# LDO.net
KiCad netlist of a schematic drawn in Altium Designer
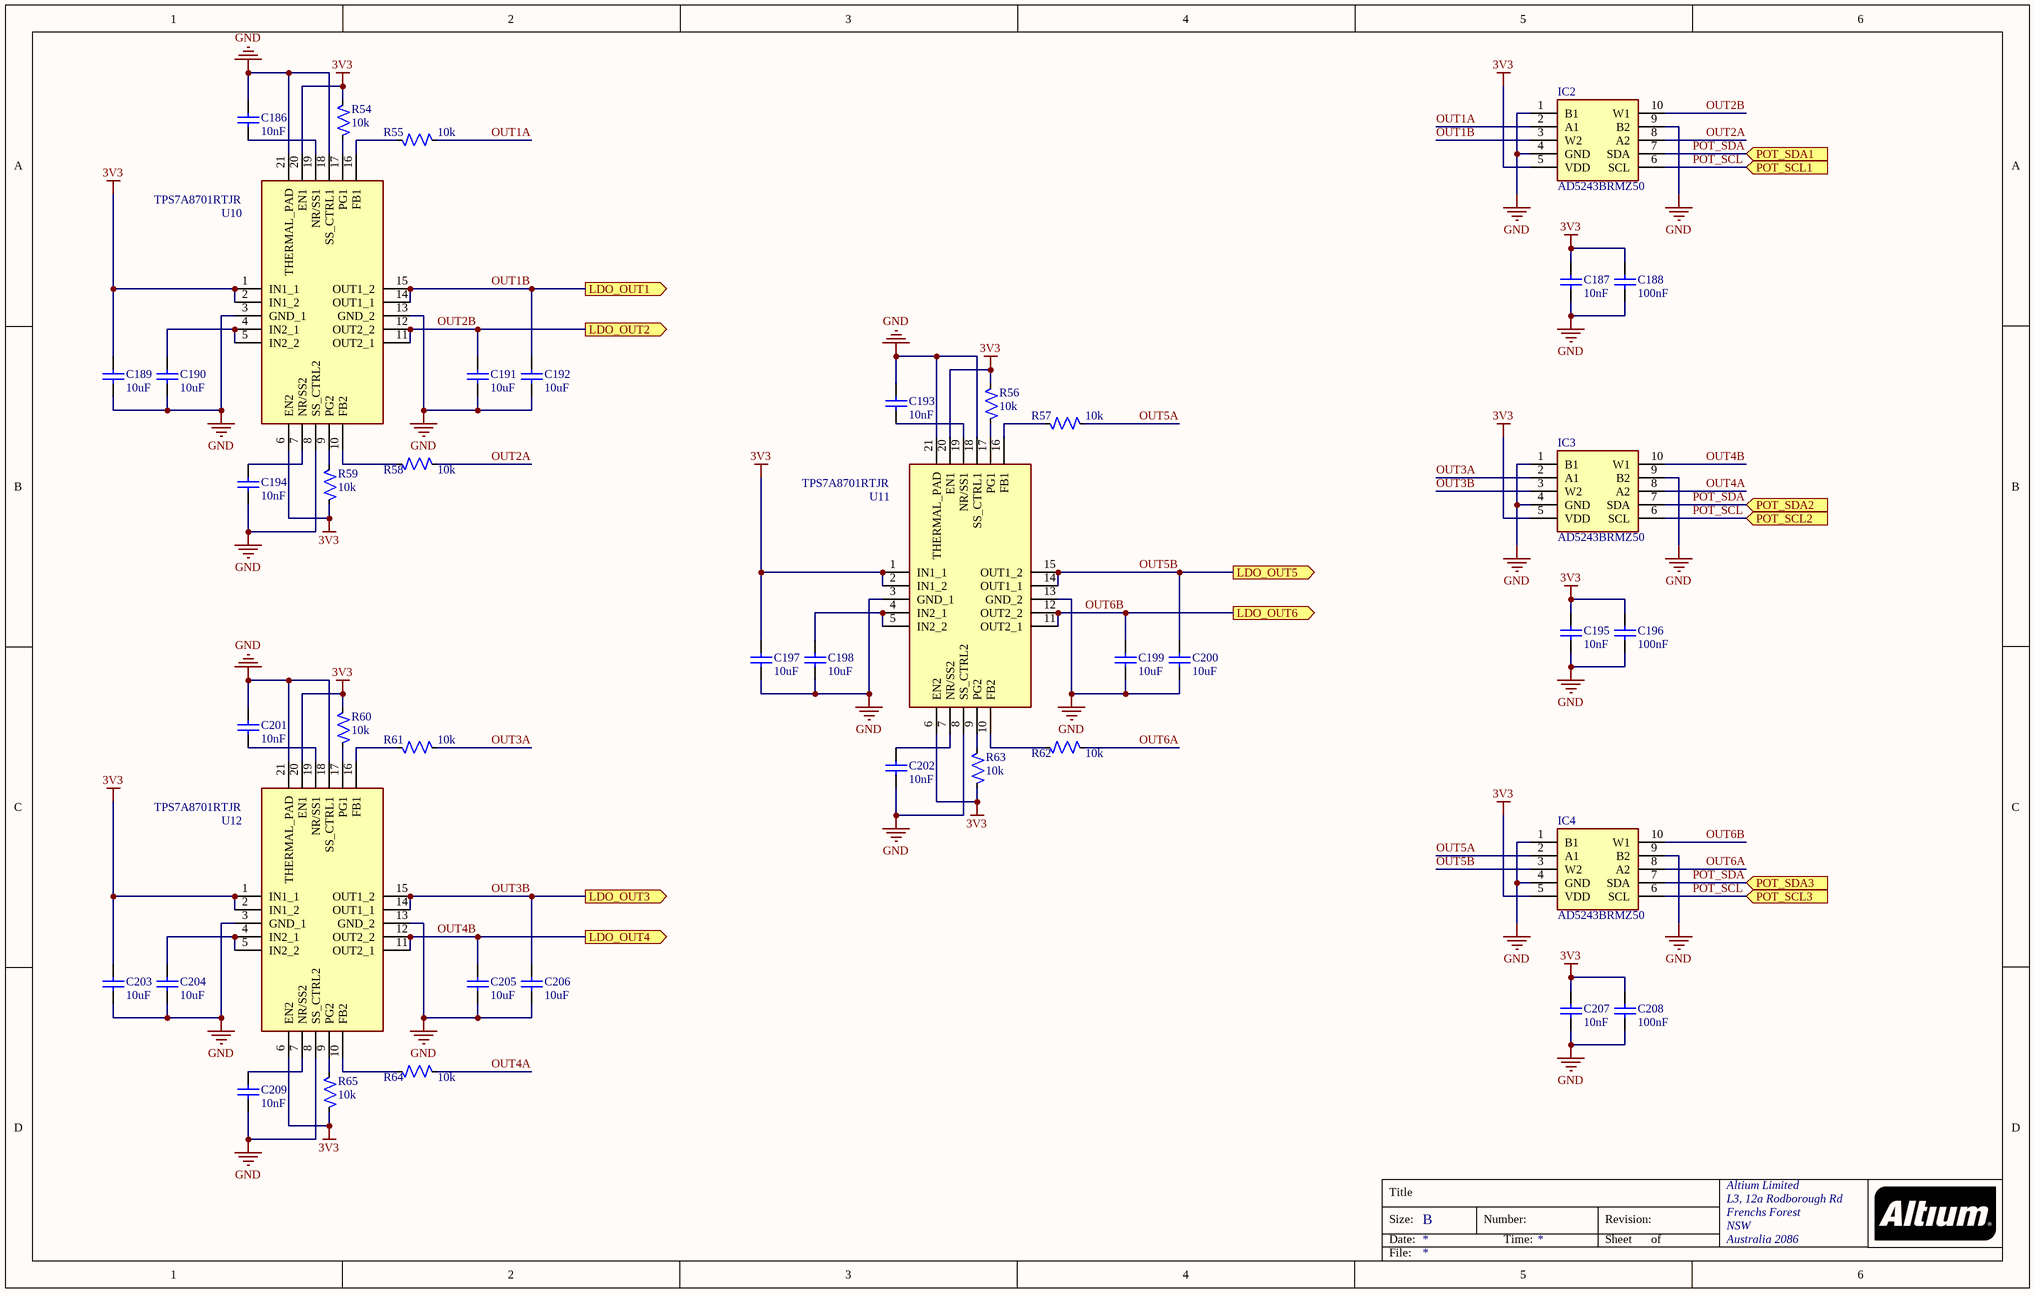
[diagram p0: LDO.SchDoc]

(export (version "E")
  (design (tool "Eeschema 10.0.6"))
  (components
    (comp (ref "C186")
      (value "10nF")
      (footprint "CAPC0402(1005)60_N")
      (libsource (lib "my_schsymbols") (part "CAP_0402"))
    )
    (comp (ref "C187")
      (value "10nF")
      (footprint "CAPC0402(1005)60_N")
      (libsource (lib "my_schsymbols") (part "CAP_0402"))
    )
    (comp (ref "C188")
      (value "100nF")
      (footprint "CAPC0402(1005)60_N")
      (libsource (lib "my_schsymbols") (part "CAP_0402"))
    )
    (comp (ref "C189")
      (value "10uF")
      (footprint "CAPC0805(2012)145_N")
      (libsource (lib "my_schsymbols") (part "CAP_0805"))
    )
    (comp (ref "C190")
      (value "10uF")
      (footprint "CAPC0805(2012)145_N")
      (libsource (lib "my_schsymbols") (part "CAP_0805"))
    )
    (comp (ref "C191")
      (value "10uF")
      (footprint "CAPC0805(2012)145_N")
      (libsource (lib "my_schsymbols") (part "CAP_0805"))
    )
    (comp (ref "C192")
      (value "10uF")
      (footprint "CAPC0805(2012)145_N")
      (libsource (lib "my_schsymbols") (part "CAP_0805"))
    )
    (comp (ref "C193")
      (value "10nF")
      (footprint "CAPC0402(1005)60_N")
      (libsource (lib "my_schsymbols") (part "CAP_0402"))
    )
    (comp (ref "C194")
      (value "10nF")
      (footprint "CAPC0402(1005)60_N")
      (libsource (lib "my_schsymbols") (part "CAP_0402"))
    )
    (comp (ref "C195")
      (value "10nF")
      (footprint "CAPC0402(1005)60_N")
      (libsource (lib "my_schsymbols") (part "CAP_0402"))
    )
    (comp (ref "C196")
      (value "100nF")
      (footprint "CAPC0402(1005)60_N")
      (libsource (lib "my_schsymbols") (part "CAP_0402"))
    )
    (comp (ref "C197")
      (value "10uF")
      (footprint "CAPC0805(2012)145_N")
      (libsource (lib "my_schsymbols") (part "CAP_0805"))
    )
    (comp (ref "C198")
      (value "10uF")
      (footprint "CAPC0805(2012)145_N")
      (libsource (lib "my_schsymbols") (part "CAP_0805"))
    )
    (comp (ref "C199")
      (value "10uF")
      (footprint "CAPC0805(2012)145_N")
      (libsource (lib "my_schsymbols") (part "CAP_0805"))
    )
    (comp (ref "C200")
      (value "10uF")
      (footprint "CAPC0805(2012)145_N")
      (libsource (lib "my_schsymbols") (part "CAP_0805"))
    )
    (comp (ref "C201")
      (value "10nF")
      (footprint "CAPC0402(1005)60_N")
      (libsource (lib "my_schsymbols") (part "CAP_0402"))
    )
    (comp (ref "C202")
      (value "10nF")
      (footprint "CAPC0402(1005)60_N")
      (libsource (lib "my_schsymbols") (part "CAP_0402"))
    )
    (comp (ref "C203")
      (value "10uF")
      (footprint "CAPC0805(2012)145_N")
      (libsource (lib "my_schsymbols") (part "CAP_0805"))
    )
    (comp (ref "C204")
      (value "10uF")
      (footprint "CAPC0805(2012)145_N")
      (libsource (lib "my_schsymbols") (part "CAP_0805"))
    )
    (comp (ref "C205")
      (value "10uF")
      (footprint "CAPC0805(2012)145_N")
      (libsource (lib "my_schsymbols") (part "CAP_0805"))
    )
    (comp (ref "C206")
      (value "10uF")
      (footprint "CAPC0805(2012)145_N")
      (libsource (lib "my_schsymbols") (part "CAP_0805"))
    )
    (comp (ref "C207")
      (value "10nF")
      (footprint "CAPC0402(1005)60_N")
      (libsource (lib "my_schsymbols") (part "CAP_0402"))
    )
    (comp (ref "C208")
      (value "100nF")
      (footprint "CAPC0402(1005)60_N")
      (libsource (lib "my_schsymbols") (part "CAP_0402"))
    )
    (comp (ref "C209")
      (value "10nF")
      (footprint "CAPC0402(1005)60_N")
      (libsource (lib "my_schsymbols") (part "CAP_0402"))
    )
    (comp (ref "IC2")
      (value "AD5243BRMZ50")
      (footprint "SamacSys:SOP50P490X110-10N")
      (description "Integrated Circuit")
      (fields
        (field (name "MOUSER PART NUMBER") "584-AD5243BRMZ50")
        (field (name "RS PART NUMBER") "9126564")
      )
      (libsource (lib "*") (part "AD5243BRMZ50"))
    )
    (comp (ref "IC3")
      (value "AD5243BRMZ50")
      (footprint "SamacSys:SOP50P490X110-10N")
      (description "Integrated Circuit")
      (fields
        (field (name "MOUSER PART NUMBER") "584-AD5243BRMZ50")
        (field (name "RS PART NUMBER") "9126564")
      )
      (libsource (lib "*") (part "AD5243BRMZ50"))
    )
    (comp (ref "IC4")
      (value "AD5243BRMZ50")
      (footprint "SamacSys:SOP50P490X110-10N")
      (description "Integrated Circuit")
      (fields
        (field (name "MOUSER PART NUMBER") "584-AD5243BRMZ50")
        (field (name "RS PART NUMBER") "9126564")
      )
      (libsource (lib "*") (part "AD5243BRMZ50"))
    )
    (comp (ref "R54")
      (value "10k")
      (footprint "RESC-0603")
      (fields
        (field (name "MFR PART NUMBER") "RC0603FR-0710KL")
        (field (name "MANUFACTURER") "Yageo")
        (field (name "TOLERANCE") "±1%")
        (field (name "CREATED BY") "murbach")
        (field (name "UPDATED BY") "murbach")
      )
      (libsource (lib "my_schsymbols") (part "RES_0603"))
    )
    (comp (ref "R55")
      (value "10k")
      (footprint "RESC-0603")
      (fields
        (field (name "MFR PART NUMBER") "RC0603FR-0710KL")
        (field (name "MANUFACTURER") "Yageo")
        (field (name "TOLERANCE") "±1%")
        (field (name "CREATED BY") "murbach")
        (field (name "UPDATED BY") "murbach")
      )
      (libsource (lib "my_schsymbols") (part "RES_0603"))
    )
    (comp (ref "R56")
      (value "10k")
      (footprint "RESC-0603")
      (fields
        (field (name "MFR PART NUMBER") "RC0603FR-0710KL")
        (field (name "MANUFACTURER") "Yageo")
        (field (name "TOLERANCE") "±1%")
        (field (name "CREATED BY") "murbach")
        (field (name "UPDATED BY") "murbach")
      )
      (libsource (lib "my_schsymbols") (part "RES_0603"))
    )
    (comp (ref "R57")
      (value "10k")
      (footprint "RESC-0603")
      (fields
        (field (name "MFR PART NUMBER") "RC0603FR-0710KL")
        (field (name "MANUFACTURER") "Yageo")
        (field (name "TOLERANCE") "±1%")
        (field (name "CREATED BY") "murbach")
        (field (name "UPDATED BY") "murbach")
      )
      (libsource (lib "my_schsymbols") (part "RES_0603"))
    )
    (comp (ref "R58")
      (value "10k")
      (footprint "RESC-0603")
      (fields
        (field (name "MFR PART NUMBER") "RC0603FR-0710KL")
        (field (name "MANUFACTURER") "Yageo")
        (field (name "TOLERANCE") "±1%")
        (field (name "CREATED BY") "murbach")
        (field (name "UPDATED BY") "murbach")
      )
      (libsource (lib "my_schsymbols") (part "RES_0603"))
    )
    (comp (ref "R59")
      (value "10k")
      (footprint "RESC-0603")
      (fields
        (field (name "MFR PART NUMBER") "RC0603FR-0710KL")
        (field (name "MANUFACTURER") "Yageo")
        (field (name "TOLERANCE") "±1%")
        (field (name "CREATED BY") "murbach")
        (field (name "UPDATED BY") "murbach")
      )
      (libsource (lib "my_schsymbols") (part "RES_0603"))
    )
    (comp (ref "R60")
      (value "10k")
      (footprint "RESC-0603")
      (fields
        (field (name "MFR PART NUMBER") "RC0603FR-0710KL")
        (field (name "MANUFACTURER") "Yageo")
        (field (name "TOLERANCE") "±1%")
        (field (name "CREATED BY") "murbach")
        (field (name "UPDATED BY") "murbach")
      )
      (libsource (lib "my_schsymbols") (part "RES_0603"))
    )
    (comp (ref "R61")
      (value "10k")
      (footprint "RESC-0603")
      (fields
        (field (name "MFR PART NUMBER") "RC0603FR-0710KL")
        (field (name "MANUFACTURER") "Yageo")
        (field (name "TOLERANCE") "±1%")
        (field (name "CREATED BY") "murbach")
        (field (name "UPDATED BY") "murbach")
      )
      (libsource (lib "my_schsymbols") (part "RES_0603"))
    )
    (comp (ref "R62")
      (value "10k")
      (footprint "RESC-0603")
      (fields
        (field (name "MFR PART NUMBER") "RC0603FR-0710KL")
        (field (name "MANUFACTURER") "Yageo")
        (field (name "TOLERANCE") "±1%")
        (field (name "CREATED BY") "murbach")
        (field (name "UPDATED BY") "murbach")
      )
      (libsource (lib "my_schsymbols") (part "RES_0603"))
    )
    (comp (ref "R63")
      (value "10k")
      (footprint "RESC-0603")
      (fields
        (field (name "MFR PART NUMBER") "RC0603FR-0710KL")
        (field (name "MANUFACTURER") "Yageo")
        (field (name "TOLERANCE") "±1%")
        (field (name "CREATED BY") "murbach")
        (field (name "UPDATED BY") "murbach")
      )
      (libsource (lib "my_schsymbols") (part "RES_0603"))
    )
    (comp (ref "R64")
      (value "10k")
      (footprint "RESC-0603")
      (fields
        (field (name "MFR PART NUMBER") "RC0603FR-0710KL")
        (field (name "MANUFACTURER") "Yageo")
        (field (name "TOLERANCE") "±1%")
        (field (name "CREATED BY") "murbach")
        (field (name "UPDATED BY") "murbach")
      )
      (libsource (lib "my_schsymbols") (part "RES_0603"))
    )
    (comp (ref "R65")
      (value "10k")
      (footprint "RESC-0603")
      (fields
        (field (name "MFR PART NUMBER") "RC0603FR-0710KL")
        (field (name "MANUFACTURER") "Yageo")
        (field (name "TOLERANCE") "±1%")
        (field (name "CREATED BY") "murbach")
        (field (name "UPDATED BY") "murbach")
      )
      (libsource (lib "my_schsymbols") (part "RES_0603"))
    )
    (comp (ref "U10")
      (value "TPS7A8701RTJR")
      (footprint "QFN50P400X400X80-21N-D")
      (description "Integrated Circuit")
      (fields (field (name "MOUSER PART NUMBER") "595-TPS7A8701RTJR"))
      (libsource (lib "my_schsymbols") (part "TPS7A8701RTJR"))
    )
    (comp (ref "U11")
      (value "TPS7A8701RTJR")
      (footprint "QFN50P400X400X80-21N-D")
      (description "Integrated Circuit")
      (fields (field (name "MOUSER PART NUMBER") "595-TPS7A8701RTJR"))
      (libsource (lib "my_schsymbols") (part "TPS7A8701RTJR"))
    )
    (comp (ref "U12")
      (value "TPS7A8701RTJR")
      (footprint "QFN50P400X400X80-21N-D")
      (description "Integrated Circuit")
      (fields (field (name "MOUSER PART NUMBER") "595-TPS7A8701RTJR"))
      (libsource (lib "my_schsymbols") (part "TPS7A8701RTJR"))
    )
  )
  (nets
    (net (code "1") (name "/OUT1A") (class "Default")
      (node (ref "IC2") (pin "2") (pinfunction "A1_2") (pintype "passive"))
      (node (ref "R55") (pin "1") (pintype "passive"))
    )
    (net (code "2") (name "/OUT1B") (class "Default")
      (node (ref "C192") (pin "2") (pinfunction "2_2") (pintype "passive"))
      (node (ref "IC2") (pin "3") (pinfunction "W2_3") (pintype "passive"))
      (node (ref "U10") (pin "14") (pinfunction "OUT1_1_14") (pintype "passive"))
      (node (ref "U10") (pin "15") (pinfunction "OUT1_2_15") (pintype "passive"))
    )
    (net (code "3") (name "/OUT2A") (class "Default")
      (node (ref "IC2") (pin "8") (pinfunction "A2_8") (pintype "passive"))
      (node (ref "R58") (pin "1") (pintype "passive"))
    )
    (net (code "4") (name "/OUT2B") (class "Default")
      (node (ref "C191") (pin "2") (pinfunction "2_2") (pintype "passive"))
      (node (ref "IC2") (pin "10") (pinfunction "W1_10") (pintype "passive"))
      (node (ref "U10") (pin "11") (pinfunction "OUT2_1_11") (pintype "passive"))
      (node (ref "U10") (pin "12") (pinfunction "OUT2_2_12") (pintype "passive"))
    )
    (net (code "5") (name "/OUT3A") (class "Default")
      (node (ref "IC3") (pin "2") (pinfunction "A1_2") (pintype "passive"))
      (node (ref "R61") (pin "1") (pintype "passive"))
    )
    (net (code "6") (name "/OUT3B") (class "Default")
      (node (ref "C206") (pin "2") (pinfunction "2_2") (pintype "passive"))
      (node (ref "IC3") (pin "3") (pinfunction "W2_3") (pintype "passive"))
      (node (ref "U12") (pin "14") (pinfunction "OUT1_1_14") (pintype "passive"))
      (node (ref "U12") (pin "15") (pinfunction "OUT1_2_15") (pintype "passive"))
    )
    (net (code "7") (name "/OUT4A") (class "Default")
      (node (ref "IC3") (pin "8") (pinfunction "A2_8") (pintype "passive"))
      (node (ref "R64") (pin "1") (pintype "passive"))
    )
    (net (code "8") (name "/OUT4B") (class "Default")
      (node (ref "C205") (pin "2") (pinfunction "2_2") (pintype "passive"))
      (node (ref "IC3") (pin "10") (pinfunction "W1_10") (pintype "passive"))
      (node (ref "U12") (pin "11") (pinfunction "OUT2_1_11") (pintype "passive"))
      (node (ref "U12") (pin "12") (pinfunction "OUT2_2_12") (pintype "passive"))
    )
    (net (code "9") (name "/OUT5A") (class "Default")
      (node (ref "IC4") (pin "2") (pinfunction "A1_2") (pintype "passive"))
      (node (ref "R57") (pin "1") (pintype "passive"))
    )
    (net (code "10") (name "/OUT5B") (class "Default")
      (node (ref "C200") (pin "2") (pinfunction "2_2") (pintype "passive"))
      (node (ref "IC4") (pin "3") (pinfunction "W2_3") (pintype "passive"))
      (node (ref "U11") (pin "14") (pinfunction "OUT1_1_14") (pintype "passive"))
      (node (ref "U11") (pin "15") (pinfunction "OUT1_2_15") (pintype "passive"))
    )
    (net (code "11") (name "/OUT6A") (class "Default")
      (node (ref "IC4") (pin "8") (pinfunction "A2_8") (pintype "passive"))
      (node (ref "R62") (pin "1") (pintype "passive"))
    )
    (net (code "12") (name "/OUT6B") (class "Default")
      (node (ref "C199") (pin "2") (pinfunction "2_2") (pintype "passive"))
      (node (ref "IC4") (pin "10") (pinfunction "W1_10") (pintype "passive"))
      (node (ref "U11") (pin "11") (pinfunction "OUT2_1_11") (pintype "passive"))
      (node (ref "U11") (pin "12") (pinfunction "OUT2_2_12") (pintype "passive"))
    )
    (net (code "13") (name "/POT_SCL") (class "Default")
      (node (ref "IC2") (pin "6") (pinfunction "SCL_6") (pintype "passive"))
      (node (ref "IC3") (pin "6") (pinfunction "SCL_6") (pintype "passive"))
      (node (ref "IC4") (pin "6") (pinfunction "SCL_6") (pintype "passive"))
    )
    (net (code "14") (name "/POT_SDA") (class "Default")
      (node (ref "IC2") (pin "7") (pinfunction "SDA_7") (pintype "passive"))
      (node (ref "IC3") (pin "7") (pinfunction "SDA_7") (pintype "passive"))
      (node (ref "IC4") (pin "7") (pinfunction "SDA_7") (pintype "passive"))
    )
    (net (code "15") (name "3V3") (class "Default")
      (node (ref "C187") (pin "2") (pinfunction "2_2") (pintype "passive"))
      (node (ref "C188") (pin "2") (pinfunction "2_2") (pintype "passive"))
      (node (ref "C189") (pin "2") (pinfunction "2_2") (pintype "passive"))
      (node (ref "C195") (pin "2") (pinfunction "2_2") (pintype "passive"))
      (node (ref "C196") (pin "2") (pinfunction "2_2") (pintype "passive"))
      (node (ref "C197") (pin "2") (pinfunction "2_2") (pintype "passive"))
      (node (ref "C203") (pin "2") (pinfunction "2_2") (pintype "passive"))
      (node (ref "C207") (pin "2") (pinfunction "2_2") (pintype "passive"))
      (node (ref "C208") (pin "2") (pinfunction "2_2") (pintype "passive"))
      (node (ref "IC2") (pin "5") (pinfunction "VDD_5") (pintype "power_in"))
      (node (ref "IC3") (pin "5") (pinfunction "VDD_5") (pintype "power_in"))
      (node (ref "IC4") (pin "5") (pinfunction "VDD_5") (pintype "power_in"))
      (node (ref "R54") (pin "2") (pintype "passive"))
      (node (ref "R56") (pin "2") (pintype "passive"))
      (node (ref "R59") (pin "1") (pintype "passive"))
      (node (ref "R60") (pin "2") (pintype "passive"))
      (node (ref "R63") (pin "1") (pintype "passive"))
      (node (ref "R65") (pin "1") (pintype "passive"))
      (node (ref "U10") (pin "1") (pinfunction "IN1_1_1") (pintype "passive"))
      (node (ref "U10") (pin "2") (pinfunction "IN1_2_2") (pintype "passive"))
      (node (ref "U10") (pin "20") (pinfunction "EN1_20") (pintype "passive"))
      (node (ref "U10") (pin "6") (pinfunction "EN2_6") (pintype "passive"))
      (node (ref "U11") (pin "1") (pinfunction "IN1_1_1") (pintype "passive"))
      (node (ref "U11") (pin "2") (pinfunction "IN1_2_2") (pintype "passive"))
      (node (ref "U11") (pin "20") (pinfunction "EN1_20") (pintype "passive"))
      (node (ref "U11") (pin "6") (pinfunction "EN2_6") (pintype "passive"))
      (node (ref "U12") (pin "1") (pinfunction "IN1_1_1") (pintype "passive"))
      (node (ref "U12") (pin "2") (pinfunction "IN1_2_2") (pintype "passive"))
      (node (ref "U12") (pin "20") (pinfunction "EN1_20") (pintype "passive"))
      (node (ref "U12") (pin "6") (pinfunction "EN2_6") (pintype "passive"))
    )
    (net (code "16") (name "GND") (class "Default")
      (node (ref "C186") (pin "2") (pinfunction "2_2") (pintype "passive"))
      (node (ref "C187") (pin "1") (pinfunction "1_1") (pintype "passive"))
      (node (ref "C188") (pin "1") (pinfunction "1_1") (pintype "passive"))
      (node (ref "C189") (pin "1") (pinfunction "1_1") (pintype "passive"))
      (node (ref "C190") (pin "1") (pinfunction "1_1") (pintype "passive"))
      (node (ref "C191") (pin "1") (pinfunction "1_1") (pintype "passive"))
      (node (ref "C192") (pin "1") (pinfunction "1_1") (pintype "passive"))
      (node (ref "C193") (pin "2") (pinfunction "2_2") (pintype "passive"))
      (node (ref "C194") (pin "1") (pinfunction "1_1") (pintype "passive"))
      (node (ref "C195") (pin "1") (pinfunction "1_1") (pintype "passive"))
      (node (ref "C196") (pin "1") (pinfunction "1_1") (pintype "passive"))
      (node (ref "C197") (pin "1") (pinfunction "1_1") (pintype "passive"))
      (node (ref "C198") (pin "1") (pinfunction "1_1") (pintype "passive"))
      (node (ref "C199") (pin "1") (pinfunction "1_1") (pintype "passive"))
      (node (ref "C200") (pin "1") (pinfunction "1_1") (pintype "passive"))
      (node (ref "C201") (pin "2") (pinfunction "2_2") (pintype "passive"))
      (node (ref "C202") (pin "1") (pinfunction "1_1") (pintype "passive"))
      (node (ref "C203") (pin "1") (pinfunction "1_1") (pintype "passive"))
      (node (ref "C204") (pin "1") (pinfunction "1_1") (pintype "passive"))
      (node (ref "C205") (pin "1") (pinfunction "1_1") (pintype "passive"))
      (node (ref "C206") (pin "1") (pinfunction "1_1") (pintype "passive"))
      (node (ref "C207") (pin "1") (pinfunction "1_1") (pintype "passive"))
      (node (ref "C208") (pin "1") (pinfunction "1_1") (pintype "passive"))
      (node (ref "C209") (pin "1") (pinfunction "1_1") (pintype "passive"))
      (node (ref "IC2") (pin "1") (pinfunction "B1_1") (pintype "passive"))
      (node (ref "IC2") (pin "4") (pinfunction "GND_4") (pintype "power_in"))
      (node (ref "IC2") (pin "9") (pinfunction "B2_9") (pintype "passive"))
      (node (ref "IC3") (pin "1") (pinfunction "B1_1") (pintype "passive"))
      (node (ref "IC3") (pin "4") (pinfunction "GND_4") (pintype "power_in"))
      (node (ref "IC3") (pin "9") (pinfunction "B2_9") (pintype "passive"))
      (node (ref "IC4") (pin "1") (pinfunction "B1_1") (pintype "passive"))
      (node (ref "IC4") (pin "4") (pinfunction "GND_4") (pintype "power_in"))
      (node (ref "IC4") (pin "9") (pinfunction "B2_9") (pintype "passive"))
      (node (ref "U10") (pin "13") (pinfunction "GND_2_13") (pintype "passive"))
      (node (ref "U10") (pin "18") (pinfunction "SS_CTRL1_18") (pintype "passive"))
      (node (ref "U10") (pin "21") (pinfunction "THERMAL_PAD_21") (pintype "passive"))
      (node (ref "U10") (pin "3") (pinfunction "GND_1_3") (pintype "passive"))
      (node (ref "U10") (pin "8") (pinfunction "SS_CTRL2_8") (pintype "passive"))
      (node (ref "U11") (pin "13") (pinfunction "GND_2_13") (pintype "passive"))
      (node (ref "U11") (pin "18") (pinfunction "SS_CTRL1_18") (pintype "passive"))
      (node (ref "U11") (pin "21") (pinfunction "THERMAL_PAD_21") (pintype "passive"))
      (node (ref "U11") (pin "3") (pinfunction "GND_1_3") (pintype "passive"))
      (node (ref "U11") (pin "8") (pinfunction "SS_CTRL2_8") (pintype "passive"))
      (node (ref "U12") (pin "13") (pinfunction "GND_2_13") (pintype "passive"))
      (node (ref "U12") (pin "18") (pinfunction "SS_CTRL1_18") (pintype "passive"))
      (node (ref "U12") (pin "21") (pinfunction "THERMAL_PAD_21") (pintype "passive"))
      (node (ref "U12") (pin "3") (pinfunction "GND_1_3") (pintype "passive"))
      (node (ref "U12") (pin "8") (pinfunction "SS_CTRL2_8") (pintype "passive"))
    )
    (net (code "17") (name "Net-(U10-FB1)") (class "Default")
      (node (ref "R55") (pin "2") (pintype "passive"))
      (node (ref "U10") (pin "16") (pinfunction "FB1_16") (pintype "passive"))
    )
    (net (code "18") (name "Net-(U10-FB2)") (class "Default")
      (node (ref "R58") (pin "2") (pintype "passive"))
      (node (ref "U10") (pin "10") (pinfunction "FB2_10") (pintype "passive"))
    )
    (net (code "19") (name "Net-(U10-IN2_1)") (class "Default")
      (node (ref "C190") (pin "2") (pinfunction "2_2") (pintype "passive"))
      (node (ref "U10") (pin "4") (pinfunction "IN2_1_4") (pintype "passive"))
      (node (ref "U10") (pin "5") (pinfunction "IN2_2_5") (pintype "passive"))
    )
    (net (code "20") (name "Net-(U10-NR{slash}SS1)") (class "Default")
      (node (ref "C186") (pin "1") (pinfunction "1_1") (pintype "passive"))
      (node (ref "U10") (pin "19") (pinfunction "NR/SS1_19") (pintype "passive"))
    )
    (net (code "21") (name "Net-(U10-NR{slash}SS2)") (class "Default")
      (node (ref "C194") (pin "2") (pinfunction "2_2") (pintype "passive"))
      (node (ref "U10") (pin "7") (pinfunction "NR/SS2_7") (pintype "passive"))
    )
    (net (code "22") (name "Net-(U10-PG1)") (class "Default")
      (node (ref "R54") (pin "1") (pintype "passive"))
      (node (ref "U10") (pin "17") (pinfunction "PG1_17") (pintype "passive"))
    )
    (net (code "23") (name "Net-(U10-PG2)") (class "Default")
      (node (ref "R59") (pin "2") (pintype "passive"))
      (node (ref "U10") (pin "9") (pinfunction "PG2_9") (pintype "passive"))
    )
    (net (code "24") (name "Net-(U11-FB1)") (class "Default")
      (node (ref "R57") (pin "2") (pintype "passive"))
      (node (ref "U11") (pin "16") (pinfunction "FB1_16") (pintype "passive"))
    )
    (net (code "25") (name "Net-(U11-FB2)") (class "Default")
      (node (ref "R62") (pin "2") (pintype "passive"))
      (node (ref "U11") (pin "10") (pinfunction "FB2_10") (pintype "passive"))
    )
    (net (code "26") (name "Net-(U11-IN2_1)") (class "Default")
      (node (ref "C198") (pin "2") (pinfunction "2_2") (pintype "passive"))
      (node (ref "U11") (pin "4") (pinfunction "IN2_1_4") (pintype "passive"))
      (node (ref "U11") (pin "5") (pinfunction "IN2_2_5") (pintype "passive"))
    )
    (net (code "27") (name "Net-(U11-NR{slash}SS1)") (class "Default")
      (node (ref "C193") (pin "1") (pinfunction "1_1") (pintype "passive"))
      (node (ref "U11") (pin "19") (pinfunction "NR/SS1_19") (pintype "passive"))
    )
    (net (code "28") (name "Net-(U11-NR{slash}SS2)") (class "Default")
      (node (ref "C202") (pin "2") (pinfunction "2_2") (pintype "passive"))
      (node (ref "U11") (pin "7") (pinfunction "NR/SS2_7") (pintype "passive"))
    )
    (net (code "29") (name "Net-(U11-PG1)") (class "Default")
      (node (ref "R56") (pin "1") (pintype "passive"))
      (node (ref "U11") (pin "17") (pinfunction "PG1_17") (pintype "passive"))
    )
    (net (code "30") (name "Net-(U11-PG2)") (class "Default")
      (node (ref "R63") (pin "2") (pintype "passive"))
      (node (ref "U11") (pin "9") (pinfunction "PG2_9") (pintype "passive"))
    )
    (net (code "31") (name "Net-(U12-FB1)") (class "Default")
      (node (ref "R61") (pin "2") (pintype "passive"))
      (node (ref "U12") (pin "16") (pinfunction "FB1_16") (pintype "passive"))
    )
    (net (code "32") (name "Net-(U12-FB2)") (class "Default")
      (node (ref "R64") (pin "2") (pintype "passive"))
      (node (ref "U12") (pin "10") (pinfunction "FB2_10") (pintype "passive"))
    )
    (net (code "33") (name "Net-(U12-IN2_1)") (class "Default")
      (node (ref "C204") (pin "2") (pinfunction "2_2") (pintype "passive"))
      (node (ref "U12") (pin "4") (pinfunction "IN2_1_4") (pintype "passive"))
      (node (ref "U12") (pin "5") (pinfunction "IN2_2_5") (pintype "passive"))
    )
    (net (code "34") (name "Net-(U12-NR{slash}SS1)") (class "Default")
      (node (ref "C201") (pin "1") (pinfunction "1_1") (pintype "passive"))
      (node (ref "U12") (pin "19") (pinfunction "NR/SS1_19") (pintype "passive"))
    )
    (net (code "35") (name "Net-(U12-NR{slash}SS2)") (class "Default")
      (node (ref "C209") (pin "2") (pinfunction "2_2") (pintype "passive"))
      (node (ref "U12") (pin "7") (pinfunction "NR/SS2_7") (pintype "passive"))
    )
    (net (code "36") (name "Net-(U12-PG1)") (class "Default")
      (node (ref "R60") (pin "1") (pintype "passive"))
      (node (ref "U12") (pin "17") (pinfunction "PG1_17") (pintype "passive"))
    )
    (net (code "37") (name "Net-(U12-PG2)") (class "Default")
      (node (ref "R65") (pin "2") (pintype "passive"))
      (node (ref "U12") (pin "9") (pinfunction "PG2_9") (pintype "passive"))
    )
  )
)
